# shift_controller.net
KiCad netlist of a schematic drawn in EAGLE
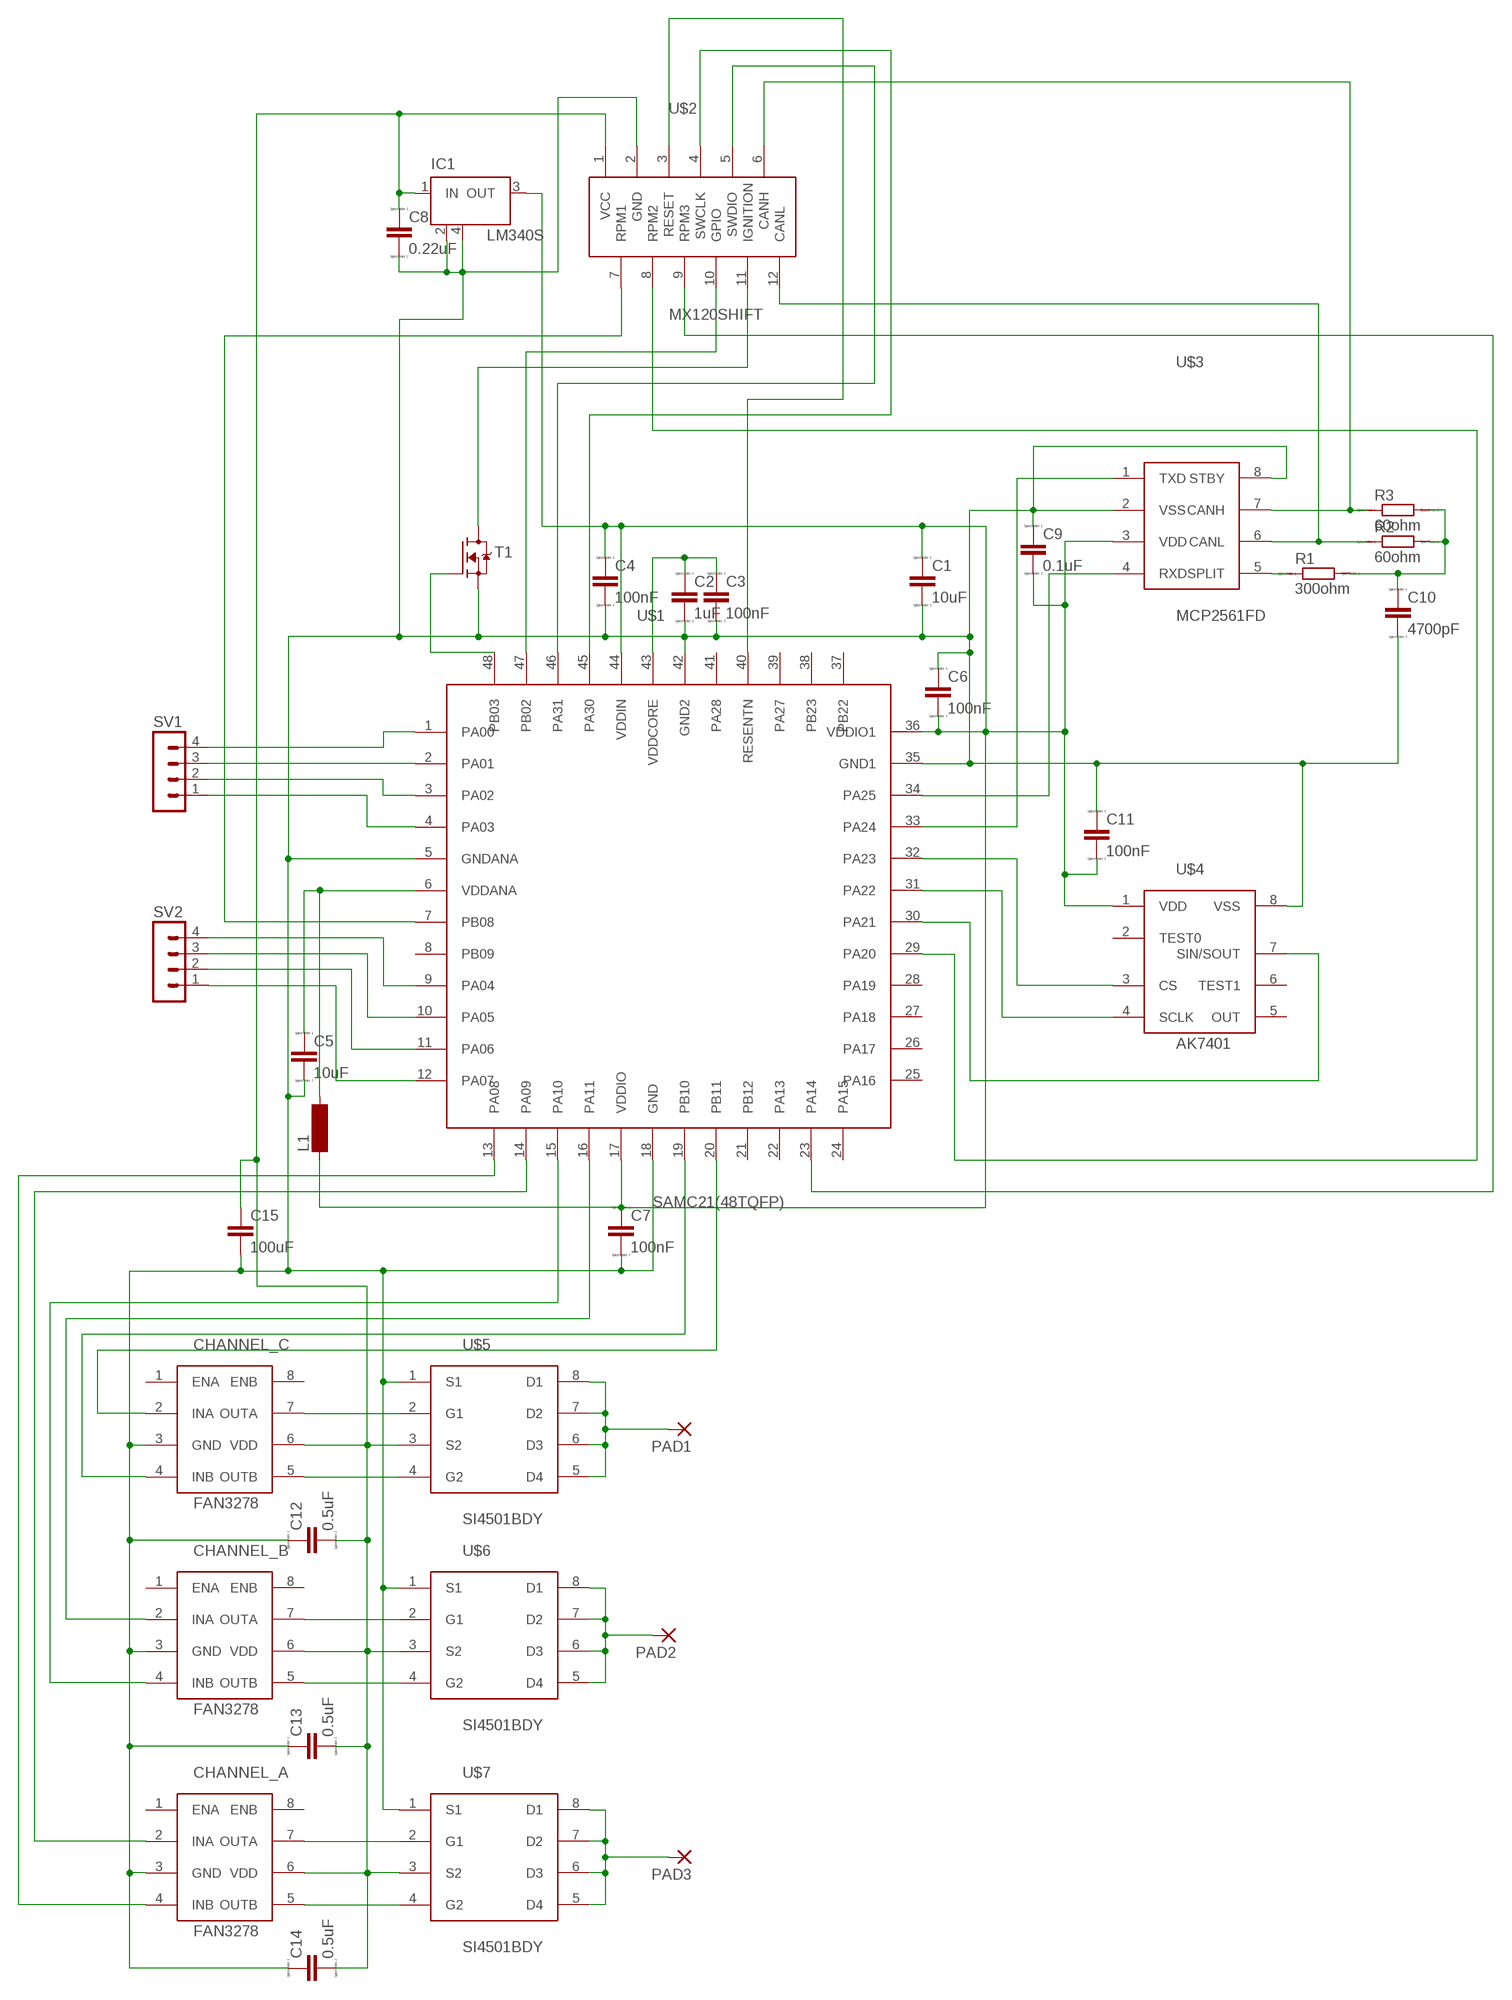
[diagram p0: schematic, sheet 1]

(export (version "E")
  (design (tool "Eeschema 10.0.6"))
  (components
    (comp (ref "C1")
      (value "10uF")
      (footprint "eagle-import:C1206")
      (libsource (lib "eagle-import") (part "CC1206"))
    )
    (comp (ref "C2")
      (value "1uF")
      (footprint "eagle-import:C1206")
      (libsource (lib "eagle-import") (part "CC1206"))
    )
    (comp (ref "C3")
      (value "100nF")
      (footprint "eagle-import:C1206")
      (libsource (lib "eagle-import") (part "CC1206"))
    )
    (comp (ref "C4")
      (value "100nF")
      (footprint "eagle-import:C1206")
      (libsource (lib "eagle-import") (part "CC1206"))
    )
    (comp (ref "C5")
      (value "10uF")
      (footprint "eagle-import:C1206")
      (libsource (lib "eagle-import") (part "CC1206"))
    )
    (comp (ref "C6")
      (value "100nF")
      (footprint "eagle-import:C1206")
      (libsource (lib "eagle-import") (part "CC1206"))
    )
    (comp (ref "C7")
      (value "100nF")
      (footprint "eagle-import:C1206")
      (libsource (lib "eagle-import") (part "CC1206"))
    )
    (comp (ref "C8")
      (value "0.22uF")
      (footprint "eagle-import:C1206")
      (libsource (lib "eagle-import") (part "CC1206"))
    )
    (comp (ref "C9")
      (value "0.1uF")
      (footprint "eagle-import:C1206")
      (libsource (lib "eagle-import") (part "CC1206"))
    )
    (comp (ref "C10")
      (value "4700pF")
      (footprint "eagle-import:C1206")
      (libsource (lib "eagle-import") (part "CC1206"))
    )
    (comp (ref "C11")
      (value "100nF")
      (footprint "eagle-import:C1206")
      (libsource (lib "eagle-import") (part "CC1206"))
    )
    (comp (ref "C12")
      (value "0.5uF")
      (footprint "eagle-import:C1206")
      (libsource (lib "eagle-import") (part "CC1206"))
    )
    (comp (ref "C13")
      (value "0.5uF")
      (footprint "eagle-import:C1206")
      (libsource (lib "eagle-import") (part "CC1206"))
    )
    (comp (ref "C14")
      (value "0.5uF")
      (footprint "eagle-import:C1206")
      (libsource (lib "eagle-import") (part "CC1206"))
    )
    (comp (ref "C15")
      (value "100uF")
      (footprint "eagle-import:C2.5-5")
      (libsource (lib "eagle-import") (part "C2.5/5"))
    )
    (comp (ref "CHANNEL_A")
      (value "FAN3278")
      (footprint "eagle-import:SOIC-8")
      (libsource (lib "eagle-import") (part "FAN3278"))
    )
    (comp (ref "CHANNEL_B")
      (value "FAN3278")
      (footprint "eagle-import:SOIC-8")
      (libsource (lib "eagle-import") (part "FAN3278"))
    )
    (comp (ref "CHANNEL_C")
      (value "FAN3278")
      (footprint "eagle-import:SOIC-8")
      (libsource (lib "eagle-import") (part "FAN3278"))
    )
    (comp (ref "IC1")
      (value "LM340S")
      (footprint "eagle-import:SOT223")
      (libsource (lib "eagle-import") (part "LM340S"))
    )
    (comp (ref "L1")
      (value "SM-1206")
      (footprint "eagle-import:SM-1206")
      (libsource (lib "eagle-import") (part "SM-1206"))
    )
    (comp (ref "PAD1")
      (value "3,81/1,4")
      (footprint "eagle-import:3,81_1,4")
      (libsource (lib "eagle-import") (part "3,81/1,4"))
    )
    (comp (ref "PAD2")
      (value "3,81/1,4")
      (footprint "eagle-import:3,81_1,4")
      (libsource (lib "eagle-import") (part "3,81/1,4"))
    )
    (comp (ref "PAD3")
      (value "3,81/1,4")
      (footprint "eagle-import:3,81_1,4")
      (libsource (lib "eagle-import") (part "3,81/1,4"))
    )
    (comp (ref "R1")
      (value "300ohm")
      (footprint "eagle-import:R1206")
      (libsource (lib "eagle-import") (part "RR1206"))
    )
    (comp (ref "R2")
      (value "60ohm")
      (footprint "eagle-import:R1206")
      (libsource (lib "eagle-import") (part "RR1206"))
    )
    (comp (ref "R3")
      (value "60ohm")
      (footprint "eagle-import:R1206")
      (libsource (lib "eagle-import") (part "RR1206"))
    )
    (comp (ref "SV1")
      (value "MA04-1")
      (footprint "eagle-import:MA04-1")
      (libsource (lib "eagle-import") (part "MA04-1"))
    )
    (comp (ref "SV2")
      (value "MA04-1")
      (footprint "eagle-import:MA04-1")
      (libsource (lib "eagle-import") (part "MA04-1"))
    )
    (comp (ref "T1")
      (value "MOSFET-N-SOT223")
      (footprint "eagle-import:SOT223")
      (libsource (lib "eagle-import") (part "MOSFET-N-SOT223"))
    )
    (comp (ref "U$1")
      (value "SAMC21(48TQFP)")
      (footprint "eagle-import:TQFP-48")
      (libsource (lib "eagle-import") (part "SAMC21(48TQFP)"))
    )
    (comp (ref "U$2")
      (value "MX120SHIFT")
      (footprint "eagle-import:12X3.5PITCH")
      (libsource (lib "eagle-import") (part "MX120SHIFT"))
    )
    (comp (ref "U$3")
      (value "MCP2561FD")
      (footprint "eagle-import:SOIC-8")
      (libsource (lib "eagle-import") (part "MCP2561FD"))
    )
    (comp (ref "U$4")
      (value "AK7401")
      (footprint "eagle-import:SOIC-8")
      (libsource (lib "eagle-import") (part "AK7401"))
    )
    (comp (ref "U$5")
      (value "SI4501BDY")
      (footprint "eagle-import:SOIC-8")
      (libsource (lib "eagle-import") (part "SI4501BDY"))
    )
    (comp (ref "U$6")
      (value "SI4501BDY")
      (footprint "eagle-import:SOIC-8")
      (libsource (lib "eagle-import") (part "SI4501BDY"))
    )
    (comp (ref "U$7")
      (value "SI4501BDY")
      (footprint "eagle-import:SOIC-8")
      (libsource (lib "eagle-import") (part "SI4501BDY"))
    )
  )
  (nets
    (net (code "1") (name "Net-(C10-Pad1)") (class "Default")
      (node (ref "C10") (pin "1") (pinfunction "1_1") (pintype "passive"))
      (node (ref "R1") (pin "2") (pinfunction "2_2") (pintype "passive"))
      (node (ref "R2") (pin "2") (pinfunction "2_2") (pintype "passive"))
      (node (ref "R3") (pin "2") (pinfunction "2_2") (pintype "passive"))
    )
    (net (code "2") (name "Net-(CHANNEL_A-GND)") (class "Default")
      (node (ref "C1") (pin "2") (pinfunction "2_2") (pintype "passive"))
      (node (ref "C10") (pin "2") (pinfunction "2_2") (pintype "passive"))
      (node (ref "C11") (pin "1") (pinfunction "1_1") (pintype "passive"))
      (node (ref "C12") (pin "1") (pinfunction "1_1") (pintype "passive"))
      (node (ref "C13") (pin "1") (pinfunction "1_1") (pintype "passive"))
      (node (ref "C14") (pin "1") (pinfunction "1_1") (pintype "passive"))
      (node (ref "C15") (pin "2") (pinfunction "2_2") (pintype "passive"))
      (node (ref "C2") (pin "2") (pinfunction "2_2") (pintype "passive"))
      (node (ref "C3") (pin "2") (pinfunction "2_2") (pintype "passive"))
      (node (ref "C4") (pin "2") (pinfunction "2_2") (pintype "passive"))
      (node (ref "C5") (pin "2") (pinfunction "2_2") (pintype "passive"))
      (node (ref "C6") (pin "1") (pinfunction "1_1") (pintype "passive"))
      (node (ref "C7") (pin "2") (pinfunction "2_2") (pintype "passive"))
      (node (ref "C8") (pin "2") (pinfunction "2_2") (pintype "passive"))
      (node (ref "C9") (pin "1") (pinfunction "1_1") (pintype "passive"))
      (node (ref "CHANNEL_A") (pin "3") (pinfunction "GND_3") (pintype "bidirectional"))
      (node (ref "CHANNEL_B") (pin "3") (pinfunction "GND_3") (pintype "bidirectional"))
      (node (ref "CHANNEL_C") (pin "3") (pinfunction "GND_3") (pintype "bidirectional"))
      (node (ref "IC1") (pin "2") (pinfunction "GND_2") (pintype "power_in"))
      (node (ref "IC1") (pin "4") (pinfunction "GND_4") (pintype "power_in"))
      (node (ref "T1") (pin "3") (pinfunction "S_3") (pintype "passive"))
      (node (ref "U$1") (pin "18") (pinfunction "GND_18") (pintype "bidirectional"))
      (node (ref "U$1") (pin "35") (pinfunction "GND1_35") (pintype "bidirectional"))
      (node (ref "U$1") (pin "42") (pinfunction "GND2_42") (pintype "bidirectional"))
      (node (ref "U$1") (pin "5") (pinfunction "GNDANA_5") (pintype "bidirectional"))
      (node (ref "U$2") (pin "2") (pinfunction "GND_2") (pintype "bidirectional"))
      (node (ref "U$3") (pin "2") (pinfunction "VSS_2") (pintype "bidirectional"))
      (node (ref "U$3") (pin "8") (pinfunction "STBY_8") (pintype "bidirectional"))
      (node (ref "U$4") (pin "8") (pinfunction "VSS_8") (pintype "bidirectional"))
      (node (ref "U$5") (pin "1") (pinfunction "S1_1") (pintype "bidirectional"))
      (node (ref "U$6") (pin "1") (pinfunction "S1_1") (pintype "bidirectional"))
      (node (ref "U$7") (pin "1") (pinfunction "S1_1") (pintype "bidirectional"))
    )
    (net (code "3") (name "Net-(CHANNEL_A-INA)") (class "Default")
      (node (ref "CHANNEL_A") (pin "2") (pinfunction "INA_2") (pintype "bidirectional"))
      (node (ref "U$1") (pin "14") (pinfunction "PA09_14") (pintype "bidirectional"))
    )
    (net (code "4") (name "Net-(CHANNEL_A-INB)") (class "Default")
      (node (ref "CHANNEL_A") (pin "4") (pinfunction "INB_4") (pintype "bidirectional"))
      (node (ref "U$1") (pin "13") (pinfunction "PA08_13") (pintype "bidirectional"))
    )
    (net (code "5") (name "Net-(CHANNEL_A-OUTA)") (class "Default")
      (node (ref "CHANNEL_A") (pin "7") (pinfunction "OUTA_7") (pintype "bidirectional"))
      (node (ref "U$7") (pin "2") (pinfunction "G1_2") (pintype "bidirectional"))
    )
    (net (code "6") (name "Net-(CHANNEL_A-OUTB)") (class "Default")
      (node (ref "CHANNEL_A") (pin "5") (pinfunction "OUTB_5") (pintype "bidirectional"))
      (node (ref "U$7") (pin "4") (pinfunction "G2_4") (pintype "bidirectional"))
    )
    (net (code "7") (name "Net-(CHANNEL_A-VDD)") (class "Default")
      (node (ref "C12") (pin "2") (pinfunction "2_2") (pintype "passive"))
      (node (ref "C13") (pin "2") (pinfunction "2_2") (pintype "passive"))
      (node (ref "C14") (pin "2") (pinfunction "2_2") (pintype "passive"))
      (node (ref "C15") (pin "1") (pinfunction "1_1") (pintype "passive"))
      (node (ref "C8") (pin "1") (pinfunction "1_1") (pintype "passive"))
      (node (ref "CHANNEL_A") (pin "6") (pinfunction "VDD_6") (pintype "bidirectional"))
      (node (ref "CHANNEL_B") (pin "6") (pinfunction "VDD_6") (pintype "bidirectional"))
      (node (ref "CHANNEL_C") (pin "6") (pinfunction "VDD_6") (pintype "bidirectional"))
      (node (ref "IC1") (pin "1") (pinfunction "IN_1") (pintype "input"))
      (node (ref "U$2") (pin "1") (pinfunction "VCC_1") (pintype "bidirectional"))
      (node (ref "U$5") (pin "3") (pinfunction "S2_3") (pintype "bidirectional"))
      (node (ref "U$6") (pin "3") (pinfunction "S2_3") (pintype "bidirectional"))
      (node (ref "U$7") (pin "3") (pinfunction "S2_3") (pintype "bidirectional"))
    )
    (net (code "8") (name "Net-(CHANNEL_B-INA)") (class "Default")
      (node (ref "CHANNEL_B") (pin "2") (pinfunction "INA_2") (pintype "bidirectional"))
      (node (ref "U$1") (pin "16") (pinfunction "PA11_16") (pintype "bidirectional"))
    )
    (net (code "9") (name "Net-(CHANNEL_B-INB)") (class "Default")
      (node (ref "CHANNEL_B") (pin "4") (pinfunction "INB_4") (pintype "bidirectional"))
      (node (ref "U$1") (pin "15") (pinfunction "PA10_15") (pintype "bidirectional"))
    )
    (net (code "10") (name "Net-(CHANNEL_B-OUTA)") (class "Default")
      (node (ref "CHANNEL_B") (pin "7") (pinfunction "OUTA_7") (pintype "bidirectional"))
      (node (ref "U$6") (pin "2") (pinfunction "G1_2") (pintype "bidirectional"))
    )
    (net (code "11") (name "Net-(CHANNEL_B-OUTB)") (class "Default")
      (node (ref "CHANNEL_B") (pin "5") (pinfunction "OUTB_5") (pintype "bidirectional"))
      (node (ref "U$6") (pin "4") (pinfunction "G2_4") (pintype "bidirectional"))
    )
    (net (code "12") (name "Net-(CHANNEL_C-INA)") (class "Default")
      (node (ref "CHANNEL_C") (pin "2") (pinfunction "INA_2") (pintype "bidirectional"))
      (node (ref "U$1") (pin "20") (pinfunction "PB11_20") (pintype "bidirectional"))
    )
    (net (code "13") (name "Net-(CHANNEL_C-INB)") (class "Default")
      (node (ref "CHANNEL_C") (pin "4") (pinfunction "INB_4") (pintype "bidirectional"))
      (node (ref "U$1") (pin "19") (pinfunction "PB10_19") (pintype "bidirectional"))
    )
    (net (code "14") (name "Net-(CHANNEL_C-OUTA)") (class "Default")
      (node (ref "CHANNEL_C") (pin "7") (pinfunction "OUTA_7") (pintype "bidirectional"))
      (node (ref "U$5") (pin "2") (pinfunction "G1_2") (pintype "bidirectional"))
    )
    (net (code "15") (name "Net-(CHANNEL_C-OUTB)") (class "Default")
      (node (ref "CHANNEL_C") (pin "5") (pinfunction "OUTB_5") (pintype "bidirectional"))
      (node (ref "U$5") (pin "4") (pinfunction "G2_4") (pintype "bidirectional"))
    )
    (net (code "16") (name "Net-(IC1-OUT)") (class "Default")
      (node (ref "C1") (pin "1") (pinfunction "1_1") (pintype "passive"))
      (node (ref "C11") (pin "2") (pinfunction "2_2") (pintype "passive"))
      (node (ref "C4") (pin "1") (pinfunction "1_1") (pintype "passive"))
      (node (ref "C6") (pin "2") (pinfunction "2_2") (pintype "passive"))
      (node (ref "C7") (pin "1") (pinfunction "1_1") (pintype "passive"))
      (node (ref "C9") (pin "2") (pinfunction "2_2") (pintype "passive"))
      (node (ref "IC1") (pin "3") (pinfunction "OUT_3") (pintype "passive"))
      (node (ref "L1") (pin "1") (pinfunction "1_1") (pintype "passive"))
      (node (ref "U$1") (pin "17") (pinfunction "VDDIO_17") (pintype "bidirectional"))
      (node (ref "U$1") (pin "36") (pinfunction "VDDIO1_36") (pintype "bidirectional"))
      (node (ref "U$1") (pin "44") (pinfunction "VDDIN_44") (pintype "bidirectional"))
      (node (ref "U$3") (pin "3") (pinfunction "VDD_3") (pintype "bidirectional"))
      (node (ref "U$4") (pin "1") (pinfunction "VDD_1") (pintype "bidirectional"))
    )
    (net (code "17") (name "Net-(PAD1-P)") (class "Default")
      (node (ref "PAD1") (pin "1") (pinfunction "P_1") (pintype "passive"))
      (node (ref "U$5") (pin "5") (pinfunction "D4_5") (pintype "bidirectional"))
      (node (ref "U$5") (pin "6") (pinfunction "D3_6") (pintype "bidirectional"))
      (node (ref "U$5") (pin "7") (pinfunction "D2_7") (pintype "bidirectional"))
      (node (ref "U$5") (pin "8") (pinfunction "D1_8") (pintype "bidirectional"))
    )
    (net (code "18") (name "Net-(PAD2-P)") (class "Default")
      (node (ref "PAD2") (pin "1") (pinfunction "P_1") (pintype "passive"))
      (node (ref "U$6") (pin "5") (pinfunction "D4_5") (pintype "bidirectional"))
      (node (ref "U$6") (pin "6") (pinfunction "D3_6") (pintype "bidirectional"))
      (node (ref "U$6") (pin "7") (pinfunction "D2_7") (pintype "bidirectional"))
      (node (ref "U$6") (pin "8") (pinfunction "D1_8") (pintype "bidirectional"))
    )
    (net (code "19") (name "Net-(PAD3-P)") (class "Default")
      (node (ref "PAD3") (pin "1") (pinfunction "P_1") (pintype "passive"))
      (node (ref "U$7") (pin "5") (pinfunction "D4_5") (pintype "bidirectional"))
      (node (ref "U$7") (pin "6") (pinfunction "D3_6") (pintype "bidirectional"))
      (node (ref "U$7") (pin "7") (pinfunction "D2_7") (pintype "bidirectional"))
      (node (ref "U$7") (pin "8") (pinfunction "D1_8") (pintype "bidirectional"))
    )
    (net (code "20") (name "Net-(T1-G)") (class "Default")
      (node (ref "T1") (pin "1") (pinfunction "G_1") (pintype "passive"))
      (node (ref "U$1") (pin "48") (pinfunction "PB03_48") (pintype "bidirectional"))
    )
    (net (code "21") (name "Net-(U$1-PA00)") (class "Default")
      (node (ref "SV1") (pin "4") (pinfunction "4_4") (pintype "passive"))
      (node (ref "U$1") (pin "1") (pinfunction "PA00_1") (pintype "bidirectional"))
    )
    (net (code "22") (name "Net-(U$1-PA01)") (class "Default")
      (node (ref "SV1") (pin "3") (pinfunction "3_3") (pintype "passive"))
      (node (ref "U$1") (pin "2") (pinfunction "PA01_2") (pintype "bidirectional"))
    )
    (net (code "23") (name "Net-(U$1-PA02)") (class "Default")
      (node (ref "SV1") (pin "2") (pinfunction "2_2") (pintype "passive"))
      (node (ref "U$1") (pin "3") (pinfunction "PA02_3") (pintype "bidirectional"))
    )
    (net (code "24") (name "Net-(U$1-PA03)") (class "Default")
      (node (ref "SV1") (pin "1") (pinfunction "1_1") (pintype "passive"))
      (node (ref "U$1") (pin "4") (pinfunction "PA03_4") (pintype "bidirectional"))
    )
    (net (code "25") (name "Net-(U$1-PA04)") (class "Default")
      (node (ref "SV2") (pin "4") (pinfunction "4_4") (pintype "passive"))
      (node (ref "U$1") (pin "9") (pinfunction "PA04_9") (pintype "bidirectional"))
    )
    (net (code "26") (name "Net-(U$1-PA05)") (class "Default")
      (node (ref "SV2") (pin "3") (pinfunction "3_3") (pintype "passive"))
      (node (ref "U$1") (pin "10") (pinfunction "PA05_10") (pintype "bidirectional"))
    )
    (net (code "27") (name "Net-(U$1-PA06)") (class "Default")
      (node (ref "SV2") (pin "2") (pinfunction "2_2") (pintype "passive"))
      (node (ref "U$1") (pin "11") (pinfunction "PA06_11") (pintype "bidirectional"))
    )
    (net (code "28") (name "Net-(U$1-PA07)") (class "Default")
      (node (ref "SV2") (pin "1") (pinfunction "1_1") (pintype "passive"))
      (node (ref "U$1") (pin "12") (pinfunction "PA07_12") (pintype "bidirectional"))
    )
    (net (code "29") (name "Net-(U$1-PA14)") (class "Default")
      (node (ref "U$1") (pin "23") (pinfunction "PA14_23") (pintype "bidirectional"))
      (node (ref "U$2") (pin "9") (pinfunction "RPM3_9") (pintype "bidirectional"))
    )
    (net (code "30") (name "Net-(U$1-PA20)") (class "Default")
      (node (ref "U$1") (pin "29") (pinfunction "PA20_29") (pintype "bidirectional"))
      (node (ref "U$2") (pin "8") (pinfunction "RPM2_8") (pintype "bidirectional"))
    )
    (net (code "31") (name "Net-(U$1-PA21)") (class "Default")
      (node (ref "U$1") (pin "30") (pinfunction "PA21_30") (pintype "bidirectional"))
      (node (ref "U$4") (pin "7") (pinfunction "SIN/SOUT_7") (pintype "bidirectional"))
    )
    (net (code "32") (name "Net-(U$1-PA22)") (class "Default")
      (node (ref "U$1") (pin "31") (pinfunction "PA22_31") (pintype "bidirectional"))
      (node (ref "U$4") (pin "4") (pinfunction "SCLK_4") (pintype "bidirectional"))
    )
    (net (code "33") (name "Net-(U$1-PA23)") (class "Default")
      (node (ref "U$1") (pin "32") (pinfunction "PA23_32") (pintype "bidirectional"))
      (node (ref "U$4") (pin "3") (pinfunction "CS_3") (pintype "bidirectional"))
    )
    (net (code "34") (name "Net-(U$1-PA24)") (class "Default")
      (node (ref "U$1") (pin "33") (pinfunction "PA24_33") (pintype "bidirectional"))
      (node (ref "U$3") (pin "1") (pinfunction "TXD_1") (pintype "bidirectional"))
    )
    (net (code "35") (name "Net-(U$1-PA25)") (class "Default")
      (node (ref "U$1") (pin "34") (pinfunction "PA25_34") (pintype "bidirectional"))
      (node (ref "U$3") (pin "4") (pinfunction "RXD_4") (pintype "bidirectional"))
    )
    (net (code "36") (name "Net-(U$1-PA30)") (class "Default")
      (node (ref "U$1") (pin "45") (pinfunction "PA30_45") (pintype "bidirectional"))
      (node (ref "U$2") (pin "4") (pinfunction "SWCLK_4") (pintype "bidirectional"))
    )
    (net (code "37") (name "Net-(U$1-PA31)") (class "Default")
      (node (ref "U$1") (pin "46") (pinfunction "PA31_46") (pintype "bidirectional"))
      (node (ref "U$2") (pin "5") (pinfunction "SWDIO_5") (pintype "bidirectional"))
    )
    (net (code "38") (name "Net-(U$1-PB02)") (class "Default")
      (node (ref "U$1") (pin "47") (pinfunction "PB02_47") (pintype "bidirectional"))
      (node (ref "U$2") (pin "10") (pinfunction "GPIO_10") (pintype "bidirectional"))
    )
    (net (code "39") (name "Net-(U$1-PB08)") (class "Default")
      (node (ref "U$1") (pin "7") (pinfunction "PB08_7") (pintype "bidirectional"))
      (node (ref "U$2") (pin "7") (pinfunction "RPM1_7") (pintype "bidirectional"))
    )
    (net (code "40") (name "Net-(U$1-RESENTN)") (class "Default")
      (node (ref "U$1") (pin "40") (pinfunction "RESENTN_40") (pintype "bidirectional"))
      (node (ref "U$2") (pin "3") (pinfunction "RESET_3") (pintype "bidirectional"))
    )
    (net (code "41") (name "Net-(U$1-VDDANA)") (class "Default")
      (node (ref "C5") (pin "1") (pinfunction "1_1") (pintype "passive"))
      (node (ref "L1") (pin "2") (pinfunction "2_2") (pintype "passive"))
      (node (ref "U$1") (pin "6") (pinfunction "VDDANA_6") (pintype "bidirectional"))
    )
    (net (code "42") (name "Net-(U$1-VDDCORE)") (class "Default")
      (node (ref "C2") (pin "1") (pinfunction "1_1") (pintype "passive"))
      (node (ref "C3") (pin "1") (pinfunction "1_1") (pintype "passive"))
      (node (ref "U$1") (pin "43") (pinfunction "VDDCORE_43") (pintype "bidirectional"))
    )
    (net (code "43") (name "Net-(U$2-CANH)") (class "Default")
      (node (ref "R3") (pin "1") (pinfunction "1_1") (pintype "passive"))
      (node (ref "U$2") (pin "6") (pinfunction "CANH_6") (pintype "bidirectional"))
      (node (ref "U$3") (pin "7") (pinfunction "CANH_7") (pintype "bidirectional"))
    )
    (net (code "44") (name "Net-(U$2-CANL)") (class "Default")
      (node (ref "R2") (pin "1") (pinfunction "1_1") (pintype "passive"))
      (node (ref "U$2") (pin "12") (pinfunction "CANL_12") (pintype "bidirectional"))
      (node (ref "U$3") (pin "6") (pinfunction "CANL_6") (pintype "bidirectional"))
    )
    (net (code "45") (name "Net-(U$2-IGNITION)") (class "Default")
      (node (ref "T1") (pin "2") (pinfunction "D_2") (pintype "passive"))
      (node (ref "T1") (pin "4") (pinfunction "D_4") (pintype "passive"))
      (node (ref "U$2") (pin "11") (pinfunction "IGNITION_11") (pintype "bidirectional"))
    )
    (net (code "46") (name "Net-(U$3-SPLIT)") (class "Default")
      (node (ref "R1") (pin "1") (pinfunction "1_1") (pintype "passive"))
      (node (ref "U$3") (pin "5") (pinfunction "SPLIT_5") (pintype "bidirectional"))
    )
    (net (code "47") (name "unconnected-(CHANNEL_A-ENA-Pad1)") (class "Default")
      (node (ref "CHANNEL_A") (pin "1") (pinfunction "ENA_1") (pintype "bidirectional"))
    )
    (net (code "48") (name "unconnected-(CHANNEL_A-ENB-Pad8)") (class "Default")
      (node (ref "CHANNEL_A") (pin "8") (pinfunction "ENB_8") (pintype "bidirectional"))
    )
    (net (code "49") (name "unconnected-(CHANNEL_B-ENA-Pad1)") (class "Default")
      (node (ref "CHANNEL_B") (pin "1") (pinfunction "ENA_1") (pintype "bidirectional"))
    )
    (net (code "50") (name "unconnected-(CHANNEL_B-ENB-Pad8)") (class "Default")
      (node (ref "CHANNEL_B") (pin "8") (pinfunction "ENB_8") (pintype "bidirectional"))
    )
    (net (code "51") (name "unconnected-(CHANNEL_C-ENA-Pad1)") (class "Default")
      (node (ref "CHANNEL_C") (pin "1") (pinfunction "ENA_1") (pintype "bidirectional"))
    )
    (net (code "52") (name "unconnected-(CHANNEL_C-ENB-Pad8)") (class "Default")
      (node (ref "CHANNEL_C") (pin "8") (pinfunction "ENB_8") (pintype "bidirectional"))
    )
    (net (code "53") (name "unconnected-(U$1-PA13-Pad22)") (class "Default")
      (node (ref "U$1") (pin "22") (pinfunction "PA13_22") (pintype "bidirectional"))
    )
    (net (code "54") (name "unconnected-(U$1-PA15-Pad24)") (class "Default")
      (node (ref "U$1") (pin "24") (pinfunction "PA15_24") (pintype "bidirectional"))
    )
    (net (code "55") (name "unconnected-(U$1-PA16-Pad25)") (class "Default")
      (node (ref "U$1") (pin "25") (pinfunction "PA16_25") (pintype "bidirectional"))
    )
    (net (code "56") (name "unconnected-(U$1-PA17-Pad26)") (class "Default")
      (node (ref "U$1") (pin "26") (pinfunction "PA17_26") (pintype "bidirectional"))
    )
    (net (code "57") (name "unconnected-(U$1-PA18-Pad27)") (class "Default")
      (node (ref "U$1") (pin "27") (pinfunction "PA18_27") (pintype "bidirectional"))
    )
    (net (code "58") (name "unconnected-(U$1-PA19-Pad28)") (class "Default")
      (node (ref "U$1") (pin "28") (pinfunction "PA19_28") (pintype "bidirectional"))
    )
    (net (code "59") (name "unconnected-(U$1-PA27-Pad39)") (class "Default")
      (node (ref "U$1") (pin "39") (pinfunction "PA27_39") (pintype "bidirectional"))
    )
    (net (code "60") (name "unconnected-(U$1-PA28-Pad41)") (class "Default")
      (node (ref "U$1") (pin "41") (pinfunction "PA28_41") (pintype "bidirectional"))
    )
    (net (code "61") (name "unconnected-(U$1-PB09-Pad8)") (class "Default")
      (node (ref "U$1") (pin "8") (pinfunction "PB09_8") (pintype "bidirectional"))
    )
    (net (code "62") (name "unconnected-(U$1-PB12-Pad21)") (class "Default")
      (node (ref "U$1") (pin "21") (pinfunction "PB12_21") (pintype "bidirectional"))
    )
    (net (code "63") (name "unconnected-(U$1-PB22-Pad37)") (class "Default")
      (node (ref "U$1") (pin "37") (pinfunction "PB22_37") (pintype "bidirectional"))
    )
    (net (code "64") (name "unconnected-(U$1-PB23-Pad38)") (class "Default")
      (node (ref "U$1") (pin "38") (pinfunction "PB23_38") (pintype "bidirectional"))
    )
    (net (code "65") (name "unconnected-(U$4-OUT-Pad5)") (class "Default")
      (node (ref "U$4") (pin "5") (pinfunction "OUT_5") (pintype "bidirectional"))
    )
    (net (code "66") (name "unconnected-(U$4-TEST0-Pad2)") (class "Default")
      (node (ref "U$4") (pin "2") (pinfunction "TEST0_2") (pintype "bidirectional"))
    )
    (net (code "67") (name "unconnected-(U$4-TEST1-Pad6)") (class "Default")
      (node (ref "U$4") (pin "6") (pinfunction "TEST1_6") (pintype "bidirectional"))
    )
  )
)
